# base.net
KiCad netlist of a schematic drawn in EAGLE
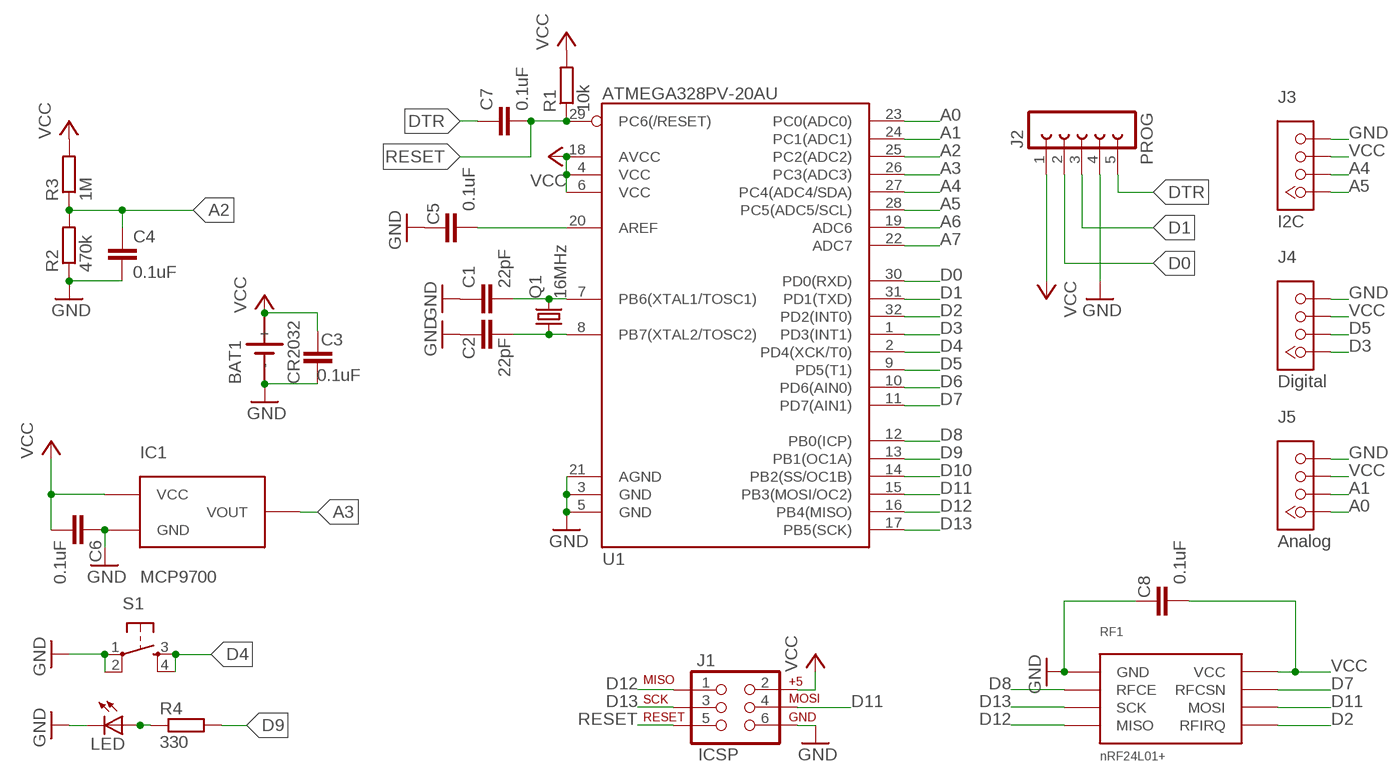
[diagram p0: schematic, sheet 1]

(export (version "E")
  (design (tool "Eeschema 10.0.6"))
  (components
    (comp (ref "BAT1")
      (value "CR2032")
      (footprint "eagle-import:SN2032")
      (libsource (lib "eagle-import") (part "SN2032"))
    )
    (comp (ref "C1")
      (value "22pF")
      (footprint "eagle-import:C0805")
      (libsource (lib "eagle-import") (part "C-EUC0805"))
    )
    (comp (ref "C2")
      (value "22pF")
      (footprint "eagle-import:C0805")
      (libsource (lib "eagle-import") (part "C-EUC0805"))
    )
    (comp (ref "C3")
      (value "0.1uF")
      (footprint "eagle-import:C0805")
      (libsource (lib "eagle-import") (part "C-EUC0805"))
    )
    (comp (ref "C4")
      (value "0.1uF")
      (footprint "eagle-import:C0805")
      (libsource (lib "eagle-import") (part "C-EUC0805"))
    )
    (comp (ref "C5")
      (value "0.1uF")
      (footprint "eagle-import:C0805")
      (libsource (lib "eagle-import") (part "C-EUC0805"))
    )
    (comp (ref "C6")
      (value "0.1uF")
      (footprint "eagle-import:C0805")
      (libsource (lib "eagle-import") (part "C-EUC0805"))
    )
    (comp (ref "C7")
      (value "0.1uF")
      (footprint "eagle-import:C0805")
      (libsource (lib "eagle-import") (part "C-EUC0805"))
    )
    (comp (ref "C8")
      (value "0.1uF")
      (footprint "eagle-import:C0805")
      (libsource (lib "eagle-import") (part "C-EUC0805"))
    )
    (comp (ref "IC1")
      (value "MCP9700")
      (footprint "eagle-import:SOT23")
      (libsource (lib "eagle-import") (part "MCP9700"))
    )
    (comp (ref "J1")
      (value "ICSP")
      (footprint "eagle-import:2X3-NS")
      (libsource (lib "eagle-import") (part "AVR_SPI_PRG_6NS"))
    )
    (comp (ref "J3")
      (value "I2C")
      (footprint "eagle-import:TWIG-4P-2.0")
      (libsource (lib "eagle-import") (part "TWIG-4P-2.0"))
    )
    (comp (ref "J4")
      (value "Digital")
      (footprint "eagle-import:TWIG-4P-2.0")
      (libsource (lib "eagle-import") (part "TWIG-4P-2.0"))
    )
    (comp (ref "J5")
      (value "Analog")
      (footprint "eagle-import:TWIG-4P-2.0")
      (libsource (lib "eagle-import") (part "TWIG-4P-2.0"))
    )
    (comp (ref "LED")
      (value "LEDCHIP-LED0805")
      (footprint "eagle-import:CHIP-LED0805")
      (libsource (lib "eagle-import") (part "LEDCHIP-LED0805"))
    )
    (comp (ref "PROG")
      (value "J2")
      (footprint "eagle-import:FE05-1")
      (libsource (lib "eagle-import") (part "FE05-1"))
    )
    (comp (ref "Q1")
      (value "16MHz")
      (footprint "eagle-import:CTS406")
      (libsource (lib "eagle-import") (part "CRYSTALCTS406"))
    )
    (comp (ref "R1")
      (value "10k")
      (footprint "eagle-import:R0805")
      (libsource (lib "eagle-import") (part "R-EU_R0805"))
    )
    (comp (ref "R2")
      (value "470k")
      (footprint "eagle-import:R0805")
      (libsource (lib "eagle-import") (part "R-EU_R0805"))
    )
    (comp (ref "R3")
      (value "1M")
      (footprint "eagle-import:R0805")
      (libsource (lib "eagle-import") (part "R-EU_R0805"))
    )
    (comp (ref "R4")
      (value "330")
      (footprint "eagle-import:R0805")
      (libsource (lib "eagle-import") (part "R-EU_R0805"))
    )
    (comp (ref "RF1")
      (value "nRF24L01+")
      (footprint "eagle-import:2X4-2.54MM")
      (libsource (lib "eagle-import") (part "NRF24L01"))
    )
    (comp (ref "S1")
      (value "TAC_SWITCHPTH")
      (footprint "eagle-import:TACTILE-PTH")
      (libsource (lib "eagle-import") (part "TAC_SWITCHPTH"))
    )
    (comp (ref "U1")
      (value "ATMEGA328PV-20AU")
      (footprint "eagle-import:TQFP32-08")
      (libsource (lib "eagle-import") (part "ATMEGA328_SMT"))
    )
  )
  (nets
    (net (code "1") (name "/A0") (class "Default")
      (node (ref "J5") (pin "P$1") (pinfunction "P$1_P$1") (pintype "bidirectional"))
      (node (ref "U1") (pin "23") (pinfunction "PC0(ADC0)_23") (pintype "bidirectional"))
    )
    (net (code "2") (name "/A1") (class "Default")
      (node (ref "J5") (pin "P$2") (pinfunction "P$2_P$2") (pintype "bidirectional"))
      (node (ref "U1") (pin "24") (pinfunction "PC1(ADC1)_24") (pintype "bidirectional"))
    )
    (net (code "3") (name "/A4") (class "Default")
      (node (ref "J3") (pin "P$2") (pinfunction "P$2_P$2") (pintype "bidirectional"))
      (node (ref "U1") (pin "27") (pinfunction "PC4(ADC4/SDA)_27") (pintype "bidirectional"))
    )
    (net (code "4") (name "/A5") (class "Default")
      (node (ref "J3") (pin "P$1") (pinfunction "P$1_P$1") (pintype "bidirectional"))
      (node (ref "U1") (pin "28") (pinfunction "PC5(ADC5/SCL)_28") (pintype "bidirectional"))
    )
    (net (code "5") (name "/A6") (class "Default")
      (node (ref "U1") (pin "19") (pinfunction "ADC6_19") (pintype "bidirectional"))
    )
    (net (code "6") (name "/A7") (class "Default")
      (node (ref "U1") (pin "22") (pinfunction "ADC7_22") (pintype "bidirectional"))
    )
    (net (code "7") (name "/D2") (class "Default")
      (node (ref "RF1") (pin "P$8") (pinfunction "RFIRQ_P$8") (pintype "output"))
      (node (ref "U1") (pin "32") (pinfunction "PD2(INT0)_32") (pintype "bidirectional"))
    )
    (net (code "8") (name "/D3") (class "Default")
      (node (ref "J4") (pin "P$1") (pinfunction "P$1_P$1") (pintype "bidirectional"))
      (node (ref "U1") (pin "1") (pinfunction "PD3(INT1)_1") (pintype "bidirectional"))
    )
    (net (code "9") (name "/D5") (class "Default")
      (node (ref "J4") (pin "P$2") (pinfunction "P$2_P$2") (pintype "bidirectional"))
      (node (ref "U1") (pin "9") (pinfunction "PD5(T1)_9") (pintype "bidirectional"))
    )
    (net (code "10") (name "/D6") (class "Default")
      (node (ref "U1") (pin "10") (pinfunction "PD6(AIN0)_10") (pintype "bidirectional"))
    )
    (net (code "11") (name "/D7") (class "Default")
      (node (ref "RF1") (pin "P$4") (pinfunction "RFCSN_P$4") (pintype "bidirectional"))
      (node (ref "U1") (pin "11") (pinfunction "PD7(AIN1)_11") (pintype "bidirectional"))
    )
    (net (code "12") (name "/D8") (class "Default")
      (node (ref "RF1") (pin "P$3") (pinfunction "RFCE_P$3") (pintype "input"))
      (node (ref "U1") (pin "12") (pinfunction "PB0(ICP)_12") (pintype "bidirectional"))
    )
    (net (code "13") (name "/D10") (class "Default")
      (node (ref "U1") (pin "14") (pinfunction "PB2(SS/OC1B)_14") (pintype "bidirectional"))
    )
    (net (code "14") (name "/D11") (class "Default")
      (node (ref "J1") (pin "4") (pinfunction "4_4") (pintype "passive"))
      (node (ref "RF1") (pin "P$6") (pinfunction "MOSI_P$6") (pintype "bidirectional"))
      (node (ref "U1") (pin "15") (pinfunction "PB3(MOSI/OC2)_15") (pintype "bidirectional"))
    )
    (net (code "15") (name "/D12") (class "Default")
      (node (ref "J1") (pin "1") (pinfunction "1_1") (pintype "passive"))
      (node (ref "RF1") (pin "P$7") (pinfunction "MISO_P$7") (pintype "bidirectional"))
      (node (ref "U1") (pin "16") (pinfunction "PB4(MISO)_16") (pintype "bidirectional"))
    )
    (net (code "16") (name "/D13") (class "Default")
      (node (ref "J1") (pin "3") (pinfunction "3_3") (pintype "passive"))
      (node (ref "RF1") (pin "P$5") (pinfunction "SCK_P$5") (pintype "input"))
      (node (ref "U1") (pin "17") (pinfunction "PB5(SCK)_17") (pintype "bidirectional"))
    )
    (net (code "17") (name "A2") (class "Default")
      (node (ref "C4") (pin "1") (pinfunction "1_1") (pintype "passive"))
      (node (ref "R2") (pin "2") (pinfunction "2_2") (pintype "passive"))
      (node (ref "R3") (pin "1") (pinfunction "1_1") (pintype "passive"))
      (node (ref "U1") (pin "25") (pinfunction "PC2(ADC2)_25") (pintype "bidirectional"))
    )
    (net (code "18") (name "A3") (class "Default")
      (node (ref "IC1") (pin "VOUT") (pinfunction "VOUT_VOUT") (pintype "output"))
      (node (ref "U1") (pin "26") (pinfunction "PC3(ADC3)_26") (pintype "bidirectional"))
    )
    (net (code "19") (name "D0") (class "Default")
      (node (ref "PROG") (pin "2") (pinfunction "2_2") (pintype "passive"))
      (node (ref "U1") (pin "30") (pinfunction "PD0(RXD)_30") (pintype "bidirectional"))
    )
    (net (code "20") (name "D1") (class "Default")
      (node (ref "PROG") (pin "3") (pinfunction "3_3") (pintype "passive"))
      (node (ref "U1") (pin "31") (pinfunction "PD1(TXD)_31") (pintype "bidirectional"))
    )
    (net (code "21") (name "D4") (class "Default")
      (node (ref "S1") (pin "3") (pinfunction "3_3") (pintype "passive"))
      (node (ref "S1") (pin "4") (pinfunction "4_4") (pintype "passive"))
      (node (ref "U1") (pin "2") (pinfunction "PD4(XCK/T0)_2") (pintype "bidirectional"))
    )
    (net (code "22") (name "D9") (class "Default")
      (node (ref "R4") (pin "2") (pinfunction "2_2") (pintype "passive"))
      (node (ref "U1") (pin "13") (pinfunction "PB1(OC1A)_13") (pintype "bidirectional"))
    )
    (net (code "23") (name "DTR") (class "Default")
      (node (ref "C7") (pin "1") (pinfunction "1_1") (pintype "passive"))
      (node (ref "PROG") (pin "5") (pinfunction "5_5") (pintype "passive"))
    )
    (net (code "24") (name "GND") (class "Default")
      (node (ref "BAT1") (pin "-") (pinfunction "-_-") (pintype "passive"))
      (node (ref "C1") (pin "1") (pinfunction "1_1") (pintype "passive"))
      (node (ref "C2") (pin "1") (pinfunction "1_1") (pintype "passive"))
      (node (ref "C3") (pin "1") (pinfunction "1_1") (pintype "passive"))
      (node (ref "C4") (pin "2") (pinfunction "2_2") (pintype "passive"))
      (node (ref "C5") (pin "2") (pinfunction "2_2") (pintype "passive"))
      (node (ref "C6") (pin "1") (pinfunction "1_1") (pintype "passive"))
      (node (ref "C8") (pin "2") (pinfunction "2_2") (pintype "passive"))
      (node (ref "IC1") (pin "GND") (pinfunction "GND_GND") (pintype "power_in"))
      (node (ref "J1") (pin "6") (pinfunction "6_6") (pintype "passive"))
      (node (ref "J3") (pin "P$4") (pinfunction "P$4_P$4") (pintype "bidirectional"))
      (node (ref "J4") (pin "P$4") (pinfunction "P$4_P$4") (pintype "bidirectional"))
      (node (ref "J5") (pin "P$4") (pinfunction "P$4_P$4") (pintype "bidirectional"))
      (node (ref "LED") (pin "C") (pinfunction "C_C") (pintype "passive"))
      (node (ref "PROG") (pin "4") (pinfunction "4_4") (pintype "passive"))
      (node (ref "R2") (pin "1") (pinfunction "1_1") (pintype "passive"))
      (node (ref "RF1") (pin "P$1") (pinfunction "GND_P$1") (pintype "power_in"))
      (node (ref "S1") (pin "1") (pinfunction "1_1") (pintype "passive"))
      (node (ref "S1") (pin "2") (pinfunction "2_2") (pintype "passive"))
      (node (ref "U1") (pin "21") (pinfunction "AGND_21") (pintype "bidirectional"))
      (node (ref "U1") (pin "3") (pinfunction "GND_3") (pintype "bidirectional"))
      (node (ref "U1") (pin "5") (pinfunction "GND_5") (pintype "bidirectional"))
    )
    (net (code "25") (name "Net-(LED-PadA)") (class "Default")
      (node (ref "LED") (pin "A") (pinfunction "A_A") (pintype "passive"))
      (node (ref "R4") (pin "1") (pinfunction "1_1") (pintype "passive"))
    )
    (net (code "26") (name "Net-(Q1-2)") (class "Default")
      (node (ref "C1") (pin "2") (pinfunction "2_2") (pintype "passive"))
      (node (ref "Q1") (pin "3") (pinfunction "2_3") (pintype "passive"))
      (node (ref "U1") (pin "7") (pinfunction "PB6(XTAL1/TOSC1)_7") (pintype "bidirectional"))
    )
    (net (code "27") (name "Net-(U1-AREF)") (class "Default")
      (node (ref "C5") (pin "1") (pinfunction "1_1") (pintype "passive"))
      (node (ref "U1") (pin "20") (pinfunction "AREF_20") (pintype "bidirectional"))
    )
    (net (code "28") (name "Net-(U1-PB7(XTAL2{slash}TOSC2))") (class "Default")
      (node (ref "C2") (pin "2") (pinfunction "2_2") (pintype "passive"))
      (node (ref "Q1") (pin "1") (pinfunction "1_1") (pintype "passive"))
      (node (ref "U1") (pin "8") (pinfunction "PB7(XTAL2/TOSC2)_8") (pintype "bidirectional"))
    )
    (net (code "29") (name "RESET") (class "Default")
      (node (ref "C7") (pin "2") (pinfunction "2_2") (pintype "passive"))
      (node (ref "J1") (pin "5") (pinfunction "5_5") (pintype "passive"))
      (node (ref "R1") (pin "1") (pinfunction "1_1") (pintype "passive"))
      (node (ref "U1") (pin "29") (pinfunction "PC6(/RESET)_29") (pintype "bidirectional"))
    )
    (net (code "30") (name "VCC") (class "Default")
      (node (ref "BAT1") (pin "+") (pinfunction "+_+") (pintype "passive"))
      (node (ref "C3") (pin "2") (pinfunction "2_2") (pintype "passive"))
      (node (ref "C6") (pin "2") (pinfunction "2_2") (pintype "passive"))
      (node (ref "C8") (pin "1") (pinfunction "1_1") (pintype "passive"))
      (node (ref "IC1") (pin "VDD") (pinfunction "VCC_VDD") (pintype "power_in"))
      (node (ref "J1") (pin "2") (pinfunction "2_2") (pintype "passive"))
      (node (ref "J3") (pin "P$3") (pinfunction "P$3_P$3") (pintype "bidirectional"))
      (node (ref "J4") (pin "P$3") (pinfunction "P$3_P$3") (pintype "bidirectional"))
      (node (ref "J5") (pin "P$3") (pinfunction "P$3_P$3") (pintype "bidirectional"))
      (node (ref "PROG") (pin "1") (pinfunction "1_1") (pintype "passive"))
      (node (ref "R1") (pin "2") (pinfunction "2_2") (pintype "passive"))
      (node (ref "R3") (pin "2") (pinfunction "2_2") (pintype "passive"))
      (node (ref "RF1") (pin "P$2") (pinfunction "VCC_P$2") (pintype "power_in"))
      (node (ref "U1") (pin "18") (pinfunction "AVCC_18") (pintype "bidirectional"))
      (node (ref "U1") (pin "4") (pinfunction "VCC_4") (pintype "bidirectional"))
      (node (ref "U1") (pin "6") (pinfunction "VCC_6") (pintype "bidirectional"))
    )
  )
)
